# MCU.net
KiCad netlist of a schematic drawn in Altium Designer
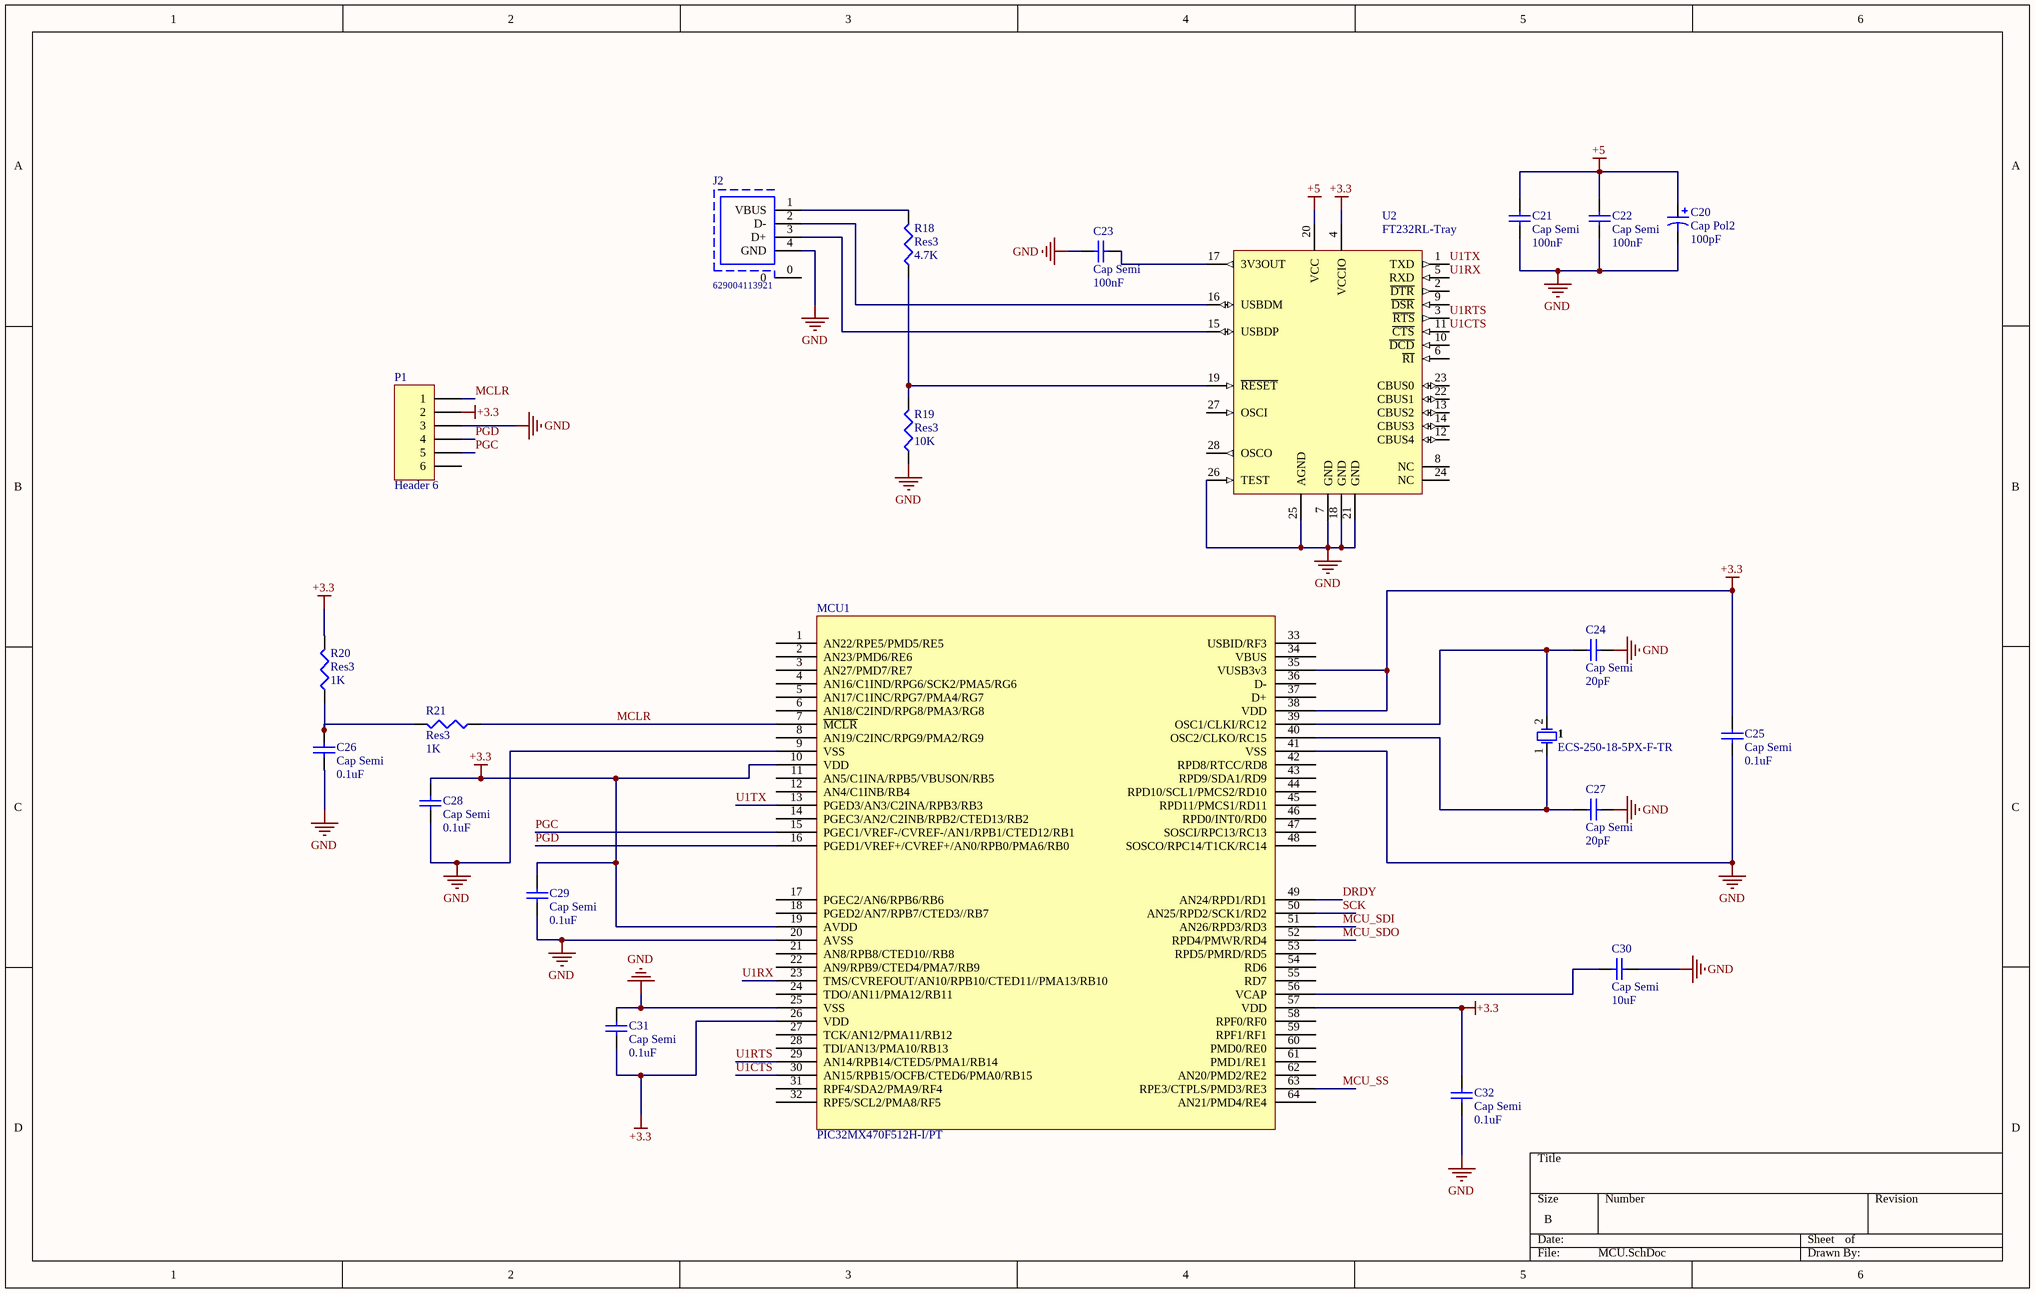
[diagram p0: MCU.SchDoc]

(export (version "E")
  (design (tool "Eeschema 10.0.6"))
  (components
    (comp (ref "1")
      (value "ECS-250-18-5PX-F-TR")
      (footprint "XTAL/S")
      (description "Low Profile Crystal, 14.7456 MHz, 18 pF, -20 to 70 degC, 2-Pin SMD, RoHS, Tape and Reel")
      (fields (field (name "MANUFACTURER") "ABRACON") (field (name "TOLERANCE") "20PPM"))
      (libsource (lib "Altium Content Vault") (part "XTAL-1-2-2"))
    )
    (comp (ref "C20")
      (value "Cap Pol2")
      (footprint "φ6.5-1")
      (description "Polarized Capacitor (Axial)")
      (fields (field (name "ALTIUM_VALUE") "100pF") (field (name "PUBLISHER") "Altium Limited"))
      (libsource (lib "Miscellaneous Devices") (part "Cap Pol2"))
    )
    (comp (ref "C21")
      (value "Cap Semi")
      (footprint "0805c")
      (description "Capacitor (Semiconductor SIM Model)")
      (fields (field (name "ALTIUM_VALUE") "100nF") (field (name "PUBLISHER") "Altium Limited"))
      (libsource (lib "Miscellaneous Devices") (part "Cap Semi"))
    )
    (comp (ref "C22")
      (value "Cap Semi")
      (footprint "0805c")
      (description "Capacitor (Semiconductor SIM Model)")
      (fields (field (name "ALTIUM_VALUE") "100nF") (field (name "PUBLISHER") "Altium Limited"))
      (libsource (lib "Miscellaneous Devices") (part "Cap Semi"))
    )
    (comp (ref "C23")
      (value "Cap Semi")
      (footprint "0805c")
      (description "Capacitor (Semiconductor SIM Model)")
      (fields (field (name "ALTIUM_VALUE") "100nF") (field (name "PUBLISHER") "Altium Limited"))
      (libsource (lib "Miscellaneous Devices") (part "Cap Semi"))
    )
    (comp (ref "C24")
      (value "Cap Semi")
      (footprint "0805c")
      (description "Capacitor (Semiconductor SIM Model)")
      (fields (field (name "ALTIUM_VALUE") "20pF") (field (name "PUBLISHER") "Altium Limited"))
      (libsource (lib "Miscellaneous Devices") (part "Cap Semi"))
    )
    (comp (ref "C25")
      (value "Cap Semi")
      (footprint "0805c")
      (description "Capacitor (Semiconductor SIM Model)")
      (fields (field (name "ALTIUM_VALUE") "0.1uF") (field (name "PUBLISHER") "Altium Limited"))
      (libsource (lib "Miscellaneous Devices") (part "Cap Semi"))
    )
    (comp (ref "C26")
      (value "Cap Semi")
      (footprint "0805c")
      (description "Capacitor (Semiconductor SIM Model)")
      (fields (field (name "ALTIUM_VALUE") "0.1uF") (field (name "PUBLISHER") "Altium Limited"))
      (libsource (lib "Miscellaneous Devices") (part "Cap Semi"))
    )
    (comp (ref "C27")
      (value "Cap Semi")
      (footprint "0805c")
      (description "Capacitor (Semiconductor SIM Model)")
      (fields (field (name "ALTIUM_VALUE") "20pF") (field (name "PUBLISHER") "Altium Limited"))
      (libsource (lib "Miscellaneous Devices") (part "Cap Semi"))
    )
    (comp (ref "C28")
      (value "Cap Semi")
      (footprint "0805c")
      (description "Capacitor (Semiconductor SIM Model)")
      (fields (field (name "ALTIUM_VALUE") "0.1uF") (field (name "PUBLISHER") "Altium Limited"))
      (libsource (lib "Miscellaneous Devices") (part "Cap Semi"))
    )
    (comp (ref "C29")
      (value "Cap Semi")
      (footprint "0805c")
      (description "Capacitor (Semiconductor SIM Model)")
      (fields (field (name "ALTIUM_VALUE") "0.1uF") (field (name "PUBLISHER") "Altium Limited"))
      (libsource (lib "Miscellaneous Devices") (part "Cap Semi"))
    )
    (comp (ref "C30")
      (value "Cap Semi")
      (footprint "0805c")
      (description "Capacitor (Semiconductor SIM Model)")
      (fields (field (name "ALTIUM_VALUE") "10uF") (field (name "PUBLISHER") "Altium Limited"))
      (libsource (lib "Miscellaneous Devices") (part "Cap Semi"))
    )
    (comp (ref "C31")
      (value "Cap Semi")
      (footprint "0805c")
      (description "Capacitor (Semiconductor SIM Model)")
      (fields (field (name "ALTIUM_VALUE") "0.1uF") (field (name "PUBLISHER") "Altium Limited"))
      (libsource (lib "Miscellaneous Devices") (part "Cap Semi"))
    )
    (comp (ref "C32")
      (value "Cap Semi")
      (footprint "0805c")
      (description "Capacitor (Semiconductor SIM Model)")
      (fields (field (name "ALTIUM_VALUE") "0.1uF") (field (name "PUBLISHER") "Altium Limited"))
      (libsource (lib "Miscellaneous Devices") (part "Cap Semi"))
    )
    (comp (ref "J2")
      (value "629004113921")
      (footprint "USB-公头")
      (description "USB 2.0 Type A Plug WR-COM, Horizontal, SMT, with Clips")
      (fields (field (name "MANUFACTURER") "Wurth Elektronik") (field (name "PUBLISHER") "WurthElektronik"))
      (libsource (lib "Altium Content Vault") (part "WE-USB-4-1SHLD"))
    )
    (comp (ref "MCU1")
      (value "PIC32MX470F512H-I/PT")
      (footprint "*QFP50P1200X1200X120-64N")
      (libsource (lib "MINTCustom") (part "PIC32MX470F512H-I/PT"))
    )
    (comp (ref "P1")
      (value "Header 6")
      (footprint "HDR1X6")
      (description "Header, 6-Pin")
      (fields (field (name "PUBLISHER") "Altium Limited"))
      (libsource (lib "Miscellaneous Connectors") (part "Header 6"))
    )
    (comp (ref "R18")
      (value "Res3")
      (footprint "0805")
      (description "Resistor")
      (fields (field (name "ALTIUM_VALUE") "4.7K") (field (name "PUBLISHER") "Altium Limited"))
      (libsource (lib "Miscellaneous Devices") (part "Res3"))
    )
    (comp (ref "R19")
      (value "Res3")
      (footprint "0805")
      (description "Resistor")
      (fields (field (name "ALTIUM_VALUE") "10K") (field (name "PUBLISHER") "Altium Limited"))
      (libsource (lib "Miscellaneous Devices") (part "Res3"))
    )
    (comp (ref "R20")
      (value "Res3")
      (footprint "0805")
      (description "Resistor")
      (fields (field (name "ALTIUM_VALUE") "1K") (field (name "PUBLISHER") "Altium Limited"))
      (libsource (lib "Miscellaneous Devices") (part "Res3"))
    )
    (comp (ref "R21")
      (value "Res3")
      (footprint "0805")
      (description "Resistor")
      (fields (field (name "ALTIUM_VALUE") "1K") (field (name "PUBLISHER") "Altium Limited"))
      (libsource (lib "Miscellaneous Devices") (part "Res3"))
    )
    (comp (ref "U2")
      (value "FT232RL-Tray")
      (footprint "SSOP-28")
      (description "USB UART Asynchronous Serial Data Transfer Chip, SSOP-28, Tray")
      (libsource (lib "altium-import") (part "root_0_COM-UART-FT232R-IL28_"))
    )
  )
  (nets
    (net (code "1") (name "+3.3") (class "Default")
      (node (ref "C25") (pin "2") (pinfunction "2_2") (pintype "passive"))
      (node (ref "C28") (pin "2") (pinfunction "2_2") (pintype "passive"))
      (node (ref "C29") (pin "2") (pinfunction "2_2") (pintype "passive"))
      (node (ref "C31") (pin "1") (pinfunction "1_1") (pintype "passive"))
      (node (ref "C32") (pin "2") (pinfunction "2_2") (pintype "passive"))
      (node (ref "MCU1") (pin "10") (pinfunction "VDD_10") (pintype "passive"))
      (node (ref "MCU1") (pin "19") (pinfunction "AVDD_19") (pintype "passive"))
      (node (ref "MCU1") (pin "26") (pinfunction "VDD_26") (pintype "passive"))
      (node (ref "MCU1") (pin "35") (pinfunction "VUSB3v3_35") (pintype "passive"))
      (node (ref "MCU1") (pin "38") (pinfunction "VDD_38") (pintype "passive"))
      (node (ref "MCU1") (pin "57") (pinfunction "VDD_57") (pintype "passive"))
      (node (ref "P1") (pin "2") (pinfunction "2_2") (pintype "passive"))
      (node (ref "R20") (pin "2") (pinfunction "2_2") (pintype "passive"))
      (node (ref "U2") (pin "4") (pinfunction "VCCIO_4") (pintype "power_in"))
    )
    (net (code "2") (name "+5") (class "Default")
      (node (ref "C20") (pin "1") (pinfunction "1_1") (pintype "passive"))
      (node (ref "C21") (pin "2") (pinfunction "2_2") (pintype "passive"))
      (node (ref "C22") (pin "2") (pinfunction "2_2") (pintype "passive"))
      (node (ref "U2") (pin "20") (pinfunction "VCC_20") (pintype "power_in"))
    )
    (net (code "3") (name "/DRDY") (class "Default")
      (node (ref "MCU1") (pin "49") (pinfunction "AN24/RPD1/RD1_49") (pintype "passive"))
    )
    (net (code "4") (name "/MCLR") (class "Default")
      (node (ref "MCU1") (pin "7") (pinfunction "~{MCLR}_7") (pintype "passive"))
      (node (ref "P1") (pin "1") (pinfunction "1_1") (pintype "passive"))
      (node (ref "R21") (pin "1") (pinfunction "1_1") (pintype "passive"))
    )
    (net (code "5") (name "/MCU_SDI") (class "Default")
      (node (ref "MCU1") (pin "51") (pinfunction "AN26/RPD3/RD3_51") (pintype "passive"))
    )
    (net (code "6") (name "/MCU_SDO") (class "Default")
      (node (ref "MCU1") (pin "52") (pinfunction "RPD4/PMWR/RD4_52") (pintype "passive"))
    )
    (net (code "7") (name "/MCU_SS") (class "Default")
      (node (ref "MCU1") (pin "63") (pinfunction "RPE3/CTPLS/PMD3/RE3_63") (pintype "passive"))
    )
    (net (code "8") (name "/PGC") (class "Default")
      (node (ref "MCU1") (pin "15") (pinfunction "PGEC1/VREF-/CVREF-/AN1/RPB1/CTED12/RB1_15") (pintype "passive"))
      (node (ref "P1") (pin "5") (pinfunction "5_5") (pintype "passive"))
    )
    (net (code "9") (name "/PGD") (class "Default")
      (node (ref "MCU1") (pin "16") (pinfunction "PGED1/VREF+/CVREF+/AN0/RPB0/PMA6/RB0_16") (pintype "passive"))
      (node (ref "P1") (pin "4") (pinfunction "4_4") (pintype "passive"))
    )
    (net (code "10") (name "/SCK") (class "Default")
      (node (ref "MCU1") (pin "50") (pinfunction "AN25/RPD2/SCK1/RD2_50") (pintype "passive"))
    )
    (net (code "11") (name "/U1CTS") (class "Default")
      (node (ref "MCU1") (pin "30") (pinfunction "AN15/RPB15/OCFB/CTED6/PMA0/RB15_30") (pintype "passive"))
      (node (ref "U2") (pin "11") (pinfunction "~{CTS}_11") (pintype "input"))
    )
    (net (code "12") (name "/U1RTS") (class "Default")
      (node (ref "MCU1") (pin "29") (pinfunction "AN14/RPB14/CTED5/PMA1/RB14_29") (pintype "passive"))
      (node (ref "U2") (pin "3") (pinfunction "~{RTS}_3") (pintype "output"))
    )
    (net (code "13") (name "/U1RX") (class "Default")
      (node (ref "MCU1") (pin "23") (pinfunction "TMS/CVREFOUT/AN10/RPB10/CTED11//PMA13/RB10_23") (pintype "passive"))
      (node (ref "U2") (pin "5") (pinfunction "RXD_5") (pintype "input"))
    )
    (net (code "14") (name "/U1TX") (class "Default")
      (node (ref "MCU1") (pin "13") (pinfunction "PGED3/AN3/C2INA/RPB3/RB3_13") (pintype "passive"))
      (node (ref "U2") (pin "1") (pinfunction "TXD_1") (pintype "output"))
    )
    (net (code "15") (name "GND") (class "Default")
      (node (ref "C20") (pin "2") (pinfunction "2_2") (pintype "passive"))
      (node (ref "C21") (pin "1") (pinfunction "1_1") (pintype "passive"))
      (node (ref "C22") (pin "1") (pinfunction "1_1") (pintype "passive"))
      (node (ref "C23") (pin "2") (pinfunction "2_2") (pintype "passive"))
      (node (ref "C24") (pin "2") (pinfunction "2_2") (pintype "passive"))
      (node (ref "C25") (pin "1") (pinfunction "1_1") (pintype "passive"))
      (node (ref "C26") (pin "1") (pinfunction "1_1") (pintype "passive"))
      (node (ref "C27") (pin "2") (pinfunction "2_2") (pintype "passive"))
      (node (ref "C28") (pin "1") (pinfunction "1_1") (pintype "passive"))
      (node (ref "C29") (pin "1") (pinfunction "1_1") (pintype "passive"))
      (node (ref "C30") (pin "2") (pinfunction "2_2") (pintype "passive"))
      (node (ref "C31") (pin "2") (pinfunction "2_2") (pintype "passive"))
      (node (ref "C32") (pin "1") (pinfunction "1_1") (pintype "passive"))
      (node (ref "J2") (pin "4") (pinfunction "GND_4") (pintype "passive"))
      (node (ref "MCU1") (pin "20") (pinfunction "AVSS_20") (pintype "passive"))
      (node (ref "MCU1") (pin "25") (pinfunction "VSS_25") (pintype "passive"))
      (node (ref "MCU1") (pin "41") (pinfunction "VSS_41") (pintype "passive"))
      (node (ref "MCU1") (pin "9") (pinfunction "VSS_9") (pintype "passive"))
      (node (ref "P1") (pin "3") (pinfunction "3_3") (pintype "passive"))
      (node (ref "R19") (pin "1") (pinfunction "1_1") (pintype "passive"))
      (node (ref "U2") (pin "18") (pinfunction "GND_18") (pintype "power_in"))
      (node (ref "U2") (pin "21") (pinfunction "GND_21") (pintype "power_in"))
      (node (ref "U2") (pin "25") (pinfunction "AGND_25") (pintype "power_in"))
      (node (ref "U2") (pin "26") (pinfunction "TEST_26") (pintype "input"))
      (node (ref "U2") (pin "7") (pinfunction "GND_7") (pintype "power_in"))
    )
    (net (code "16") (name "Net-(C26-Pad2)") (class "Default")
      (node (ref "C26") (pin "2") (pinfunction "2_2") (pintype "passive"))
      (node (ref "R20") (pin "1") (pinfunction "1_1") (pintype "passive"))
      (node (ref "R21") (pin "2") (pinfunction "2_2") (pintype "passive"))
    )
    (net (code "17") (name "Net-(J2-D+)") (class "Default")
      (node (ref "J2") (pin "3") (pinfunction "D+_3") (pintype "passive"))
      (node (ref "U2") (pin "15") (pinfunction "USBDP_15") (pintype "bidirectional"))
    )
    (net (code "18") (name "Net-(J2-D-)") (class "Default")
      (node (ref "J2") (pin "2") (pinfunction "D-_2") (pintype "passive"))
      (node (ref "U2") (pin "16") (pinfunction "USBDM_16") (pintype "bidirectional"))
    )
    (net (code "19") (name "Net-(J2-VBUS)") (class "Default")
      (node (ref "J2") (pin "1") (pinfunction "VBUS_1") (pintype "passive"))
      (node (ref "R18") (pin "2") (pinfunction "2_2") (pintype "passive"))
    )
    (net (code "20") (name "Net-(MCU1-OSC1{slash}CLKI{slash}RC12)") (class "Default")
      (node (ref "1") (pin "2") (pinfunction "2_2") (pintype "passive"))
      (node (ref "C24") (pin "1") (pinfunction "1_1") (pintype "passive"))
      (node (ref "MCU1") (pin "39") (pinfunction "OSC1/CLKI/RC12_39") (pintype "passive"))
    )
    (net (code "21") (name "Net-(MCU1-OSC2{slash}CLKO{slash}RC15)") (class "Default")
      (node (ref "1") (pin "1") (pinfunction "1_1") (pintype "passive"))
      (node (ref "C27") (pin "1") (pinfunction "1_1") (pintype "passive"))
      (node (ref "MCU1") (pin "40") (pinfunction "OSC2/CLKO/RC15_40") (pintype "passive"))
    )
    (net (code "22") (name "Net-(MCU1-VCAP)") (class "Default")
      (node (ref "C30") (pin "1") (pinfunction "1_1") (pintype "passive"))
      (node (ref "MCU1") (pin "56") (pinfunction "VCAP_56") (pintype "passive"))
    )
    (net (code "23") (name "Net-(U2-3V3OUT)") (class "Default")
      (node (ref "C23") (pin "1") (pinfunction "1_1") (pintype "passive"))
      (node (ref "U2") (pin "17") (pinfunction "3V3OUT_17") (pintype "output"))
    )
    (net (code "24") (name "Net-(U2-~{RESET})") (class "Default")
      (node (ref "R18") (pin "1") (pinfunction "1_1") (pintype "passive"))
      (node (ref "R19") (pin "2") (pinfunction "2_2") (pintype "passive"))
      (node (ref "U2") (pin "19") (pinfunction "~{RESET}_19") (pintype "input"))
    )
    (net (code "25") (name "unconnected-(J2-Pad0)") (class "Default")
      (node (ref "J2") (pin "0") (pinfunction "0_0") (pintype "passive"))
    )
    (net (code "26") (name "unconnected-(MCU1-AN4{slash}C1INB{slash}RB4-Pad12)") (class "Default")
      (node (ref "MCU1") (pin "12") (pinfunction "AN4/C1INB/RB4_12") (pintype "passive"))
    )
    (net (code "27") (name "unconnected-(MCU1-AN5{slash}C1INA{slash}RPB5{slash}VBUSON{slash}RB5-Pad11)") (class "Default")
      (node (ref "MCU1") (pin "11") (pinfunction "AN5/C1INA/RPB5/VBUSON/RB5_11") (pintype "passive"))
    )
    (net (code "28") (name "unconnected-(MCU1-AN8{slash}RPB8{slash}CTED10{slash}{slash}RB8-Pad21)") (class "Default")
      (node (ref "MCU1") (pin "21") (pinfunction "AN8/RPB8/CTED10//RB8_21") (pintype "passive"))
    )
    (net (code "29") (name "unconnected-(MCU1-AN9{slash}RPB9{slash}CTED4{slash}PMA7{slash}RB9-Pad22)") (class "Default")
      (node (ref "MCU1") (pin "22") (pinfunction "AN9/RPB9/CTED4/PMA7/RB9_22") (pintype "passive"))
    )
    (net (code "30") (name "unconnected-(MCU1-AN16{slash}C1IND{slash}RPG6{slash}SCK2{slash}PMA5{slash}RG6-Pad4)") (class "Default")
      (node (ref "MCU1") (pin "4") (pinfunction "AN16/C1IND/RPG6/SCK2/PMA5/RG6_4") (pintype "passive"))
    )
    (net (code "31") (name "unconnected-(MCU1-AN17{slash}C1INC{slash}RPG7{slash}PMA4{slash}RG7-Pad5)") (class "Default")
      (node (ref "MCU1") (pin "5") (pinfunction "AN17/C1INC/RPG7/PMA4/RG7_5") (pintype "passive"))
    )
    (net (code "32") (name "unconnected-(MCU1-AN18{slash}C2IND{slash}RPG8{slash}PMA3{slash}RG8-Pad6)") (class "Default")
      (node (ref "MCU1") (pin "6") (pinfunction "AN18/C2IND/RPG8/PMA3/RG8_6") (pintype "passive"))
    )
    (net (code "33") (name "unconnected-(MCU1-AN19{slash}C2INC{slash}RPG9{slash}PMA2{slash}RG9-Pad8)") (class "Default")
      (node (ref "MCU1") (pin "8") (pinfunction "AN19/C2INC/RPG9/PMA2/RG9_8") (pintype "passive"))
    )
    (net (code "34") (name "unconnected-(MCU1-AN20{slash}PMD2{slash}RE2-Pad62)") (class "Default")
      (node (ref "MCU1") (pin "62") (pinfunction "AN20/PMD2/RE2_62") (pintype "passive"))
    )
    (net (code "35") (name "unconnected-(MCU1-AN21{slash}PMD4{slash}RE4-Pad64)") (class "Default")
      (node (ref "MCU1") (pin "64") (pinfunction "AN21/PMD4/RE4_64") (pintype "passive"))
    )
    (net (code "36") (name "unconnected-(MCU1-AN22{slash}RPE5{slash}PMD5{slash}RE5-Pad1)") (class "Default")
      (node (ref "MCU1") (pin "1") (pinfunction "AN22/RPE5/PMD5/RE5_1") (pintype "passive"))
    )
    (net (code "37") (name "unconnected-(MCU1-AN23{slash}PMD6{slash}RE6-Pad2)") (class "Default")
      (node (ref "MCU1") (pin "2") (pinfunction "AN23/PMD6/RE6_2") (pintype "passive"))
    )
    (net (code "38") (name "unconnected-(MCU1-AN27{slash}PMD7{slash}RE7-Pad3)") (class "Default")
      (node (ref "MCU1") (pin "3") (pinfunction "AN27/PMD7/RE7_3") (pintype "passive"))
    )
    (net (code "39") (name "unconnected-(MCU1-D+-Pad37)") (class "Default")
      (node (ref "MCU1") (pin "37") (pinfunction "D+_37") (pintype "passive"))
    )
    (net (code "40") (name "unconnected-(MCU1-D--Pad36)") (class "Default")
      (node (ref "MCU1") (pin "36") (pinfunction "D-_36") (pintype "passive"))
    )
    (net (code "41") (name "unconnected-(MCU1-PGEC2{slash}AN6{slash}RPB6{slash}RB6-Pad17)") (class "Default")
      (node (ref "MCU1") (pin "17") (pinfunction "PGEC2/AN6/RPB6/RB6_17") (pintype "passive"))
    )
    (net (code "42") (name "unconnected-(MCU1-PGEC3{slash}AN2{slash}C2INB{slash}RPB2{slash}CTED13{slash}RB2-Pad14)") (class "Default")
      (node (ref "MCU1") (pin "14") (pinfunction "PGEC3/AN2/C2INB/RPB2/CTED13/RB2_14") (pintype "passive"))
    )
    (net (code "43") (name "unconnected-(MCU1-PGED2{slash}AN7{slash}RPB7{slash}CTED3{slash}{slash}RB7-Pad18)") (class "Default")
      (node (ref "MCU1") (pin "18") (pinfunction "PGED2/AN7/RPB7/CTED3//RB7_18") (pintype "passive"))
    )
    (net (code "44") (name "unconnected-(MCU1-PMD0{slash}RE0-Pad60)") (class "Default")
      (node (ref "MCU1") (pin "60") (pinfunction "PMD0/RE0_60") (pintype "passive"))
    )
    (net (code "45") (name "unconnected-(MCU1-PMD1{slash}RE1-Pad61)") (class "Default")
      (node (ref "MCU1") (pin "61") (pinfunction "PMD1/RE1_61") (pintype "passive"))
    )
    (net (code "46") (name "unconnected-(MCU1-RD6-Pad54)") (class "Default")
      (node (ref "MCU1") (pin "54") (pinfunction "RD6_54") (pintype "passive"))
    )
    (net (code "47") (name "unconnected-(MCU1-RD7-Pad55)") (class "Default")
      (node (ref "MCU1") (pin "55") (pinfunction "RD7_55") (pintype "passive"))
    )
    (net (code "48") (name "unconnected-(MCU1-RPD0{slash}INT0{slash}RD0-Pad46)") (class "Default")
      (node (ref "MCU1") (pin "46") (pinfunction "RPD0/INT0/RD0_46") (pintype "passive"))
    )
    (net (code "49") (name "unconnected-(MCU1-RPD5{slash}PMRD{slash}RD5-Pad53)") (class "Default")
      (node (ref "MCU1") (pin "53") (pinfunction "RPD5/PMRD/RD5_53") (pintype "passive"))
    )
    (net (code "50") (name "unconnected-(MCU1-RPD8{slash}RTCC{slash}RD8-Pad42)") (class "Default")
      (node (ref "MCU1") (pin "42") (pinfunction "RPD8/RTCC/RD8_42") (pintype "passive"))
    )
    (net (code "51") (name "unconnected-(MCU1-RPD9{slash}SDA1{slash}RD9-Pad43)") (class "Default")
      (node (ref "MCU1") (pin "43") (pinfunction "RPD9/SDA1/RD9_43") (pintype "passive"))
    )
    (net (code "52") (name "unconnected-(MCU1-RPD10{slash}SCL1{slash}PMCS2{slash}RD10-Pad44)") (class "Default")
      (node (ref "MCU1") (pin "44") (pinfunction "RPD10/SCL1/PMCS2/RD10_44") (pintype "passive"))
    )
    (net (code "53") (name "unconnected-(MCU1-RPD11{slash}PMCS1{slash}RD11-Pad45)") (class "Default")
      (node (ref "MCU1") (pin "45") (pinfunction "RPD11/PMCS1/RD11_45") (pintype "passive"))
    )
    (net (code "54") (name "unconnected-(MCU1-RPF0{slash}RF0-Pad58)") (class "Default")
      (node (ref "MCU1") (pin "58") (pinfunction "RPF0/RF0_58") (pintype "passive"))
    )
    (net (code "55") (name "unconnected-(MCU1-RPF1{slash}RF1-Pad59)") (class "Default")
      (node (ref "MCU1") (pin "59") (pinfunction "RPF1/RF1_59") (pintype "passive"))
    )
    (net (code "56") (name "unconnected-(MCU1-RPF4{slash}SDA2{slash}PMA9{slash}RF4-Pad31)") (class "Default")
      (node (ref "MCU1") (pin "31") (pinfunction "RPF4/SDA2/PMA9/RF4_31") (pintype "passive"))
    )
    (net (code "57") (name "unconnected-(MCU1-RPF5{slash}SCL2{slash}PMA8{slash}RF5-Pad32)") (class "Default")
      (node (ref "MCU1") (pin "32") (pinfunction "RPF5/SCL2/PMA8/RF5_32") (pintype "passive"))
    )
    (net (code "58") (name "unconnected-(MCU1-SOSCI{slash}RPC13{slash}RC13-Pad47)") (class "Default")
      (node (ref "MCU1") (pin "47") (pinfunction "SOSCI/RPC13/RC13_47") (pintype "passive"))
    )
    (net (code "59") (name "unconnected-(MCU1-SOSCO{slash}RPC14{slash}T1CK{slash}RC14-Pad48)") (class "Default")
      (node (ref "MCU1") (pin "48") (pinfunction "SOSCO/RPC14/T1CK/RC14_48") (pintype "passive"))
    )
    (net (code "60") (name "unconnected-(MCU1-TCK{slash}AN12{slash}PMA11{slash}RB12-Pad27)") (class "Default")
      (node (ref "MCU1") (pin "27") (pinfunction "TCK/AN12/PMA11/RB12_27") (pintype "passive"))
    )
    (net (code "61") (name "unconnected-(MCU1-TDI{slash}AN13{slash}PMA10{slash}RB13-Pad28)") (class "Default")
      (node (ref "MCU1") (pin "28") (pinfunction "TDI/AN13/PMA10/RB13_28") (pintype "passive"))
    )
    (net (code "62") (name "unconnected-(MCU1-TDO{slash}AN11{slash}PMA12{slash}RB11-Pad24)") (class "Default")
      (node (ref "MCU1") (pin "24") (pinfunction "TDO/AN11/PMA12/RB11_24") (pintype "passive"))
    )
    (net (code "63") (name "unconnected-(MCU1-USBID{slash}RF3-Pad33)") (class "Default")
      (node (ref "MCU1") (pin "33") (pinfunction "USBID/RF3_33") (pintype "passive"))
    )
    (net (code "64") (name "unconnected-(MCU1-VBUS-Pad34)") (class "Default")
      (node (ref "MCU1") (pin "34") (pinfunction "VBUS_34") (pintype "passive"))
    )
    (net (code "65") (name "unconnected-(P1-Pad6)") (class "Default")
      (node (ref "P1") (pin "6") (pinfunction "6_6") (pintype "passive"))
    )
    (net (code "66") (name "unconnected-(U2-CBUS0-Pad23)") (class "Default")
      (node (ref "U2") (pin "23") (pinfunction "CBUS0_23") (pintype "bidirectional"))
    )
    (net (code "67") (name "unconnected-(U2-CBUS1-Pad22)") (class "Default")
      (node (ref "U2") (pin "22") (pinfunction "CBUS1_22") (pintype "bidirectional"))
    )
    (net (code "68") (name "unconnected-(U2-CBUS2-Pad13)") (class "Default")
      (node (ref "U2") (pin "13") (pinfunction "CBUS2_13") (pintype "bidirectional"))
    )
    (net (code "69") (name "unconnected-(U2-CBUS3-Pad14)") (class "Default")
      (node (ref "U2") (pin "14") (pinfunction "CBUS3_14") (pintype "bidirectional"))
    )
    (net (code "70") (name "unconnected-(U2-CBUS4-Pad12)") (class "Default")
      (node (ref "U2") (pin "12") (pinfunction "CBUS4_12") (pintype "bidirectional"))
    )
    (net (code "71") (name "unconnected-(U2-NC-Pad8)") (class "Default")
      (node (ref "U2") (pin "8") (pinfunction "NC_8") (pintype "passive"))
    )
    (net (code "72") (name "unconnected-(U2-NC-Pad24)") (class "Default")
      (node (ref "U2") (pin "24") (pinfunction "NC_24") (pintype "passive"))
    )
    (net (code "73") (name "unconnected-(U2-OSCI-Pad27)") (class "Default")
      (node (ref "U2") (pin "27") (pinfunction "OSCI_27") (pintype "input"))
    )
    (net (code "74") (name "unconnected-(U2-OSCO-Pad28)") (class "Default")
      (node (ref "U2") (pin "28") (pinfunction "OSCO_28") (pintype "output"))
    )
    (net (code "75") (name "unconnected-(U2-~{DCD}-Pad10)") (class "Default")
      (node (ref "U2") (pin "10") (pinfunction "~{DCD}_10") (pintype "input"))
    )
    (net (code "76") (name "unconnected-(U2-~{DSR}-Pad9)") (class "Default")
      (node (ref "U2") (pin "9") (pinfunction "~{DSR}_9") (pintype "input"))
    )
    (net (code "77") (name "unconnected-(U2-~{DTR}-Pad2)") (class "Default")
      (node (ref "U2") (pin "2") (pinfunction "~{DTR}_2") (pintype "output"))
    )
    (net (code "78") (name "unconnected-(U2-~{RI}-Pad6)") (class "Default")
      (node (ref "U2") (pin "6") (pinfunction "~{RI}_6") (pintype "input"))
    )
  )
)
